# ADUM1250ARZ_v_01.net
KiCad netlist of a schematic drawn in EAGLE
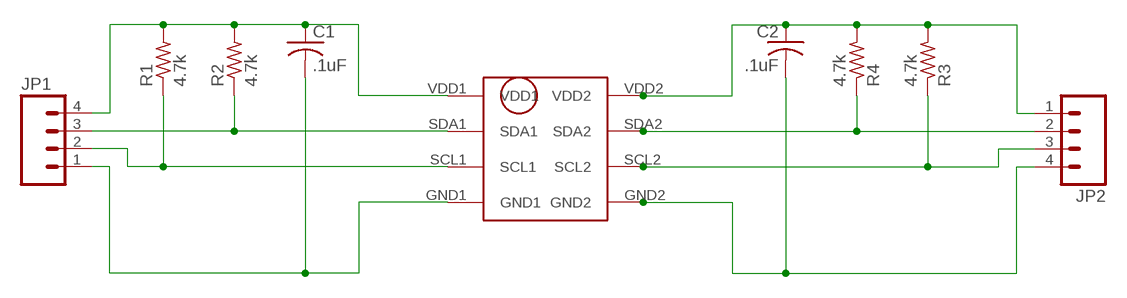
[diagram p0: schematic, sheet 1]

(export (version "E")
  (design (tool "Eeschema 10.0.6"))
  (components
    (comp (ref "C1")
      (value ".1uF")
      (footprint "eagle-import:C0805")
      (libsource (lib "eagle-import") (part "C-USC0805"))
    )
    (comp (ref "C2")
      (value ".1uF")
      (footprint "eagle-import:C0805")
      (libsource (lib "eagle-import") (part "C-USC0805"))
    )
    (comp (ref "JP1")
      (value "M04PTH")
      (footprint "eagle-import:1X04")
      (libsource (lib "eagle-import") (part "M04PTH"))
    )
    (comp (ref "JP2")
      (value "M04PTH")
      (footprint "eagle-import:1X04")
      (libsource (lib "eagle-import") (part "M04PTH"))
    )
    (comp (ref "R1")
      (value "4.7k")
      (footprint "eagle-import:R0805")
      (libsource (lib "eagle-import") (part "R-US_R0805"))
    )
    (comp (ref "R2")
      (value "4.7k")
      (footprint "eagle-import:R0805")
      (libsource (lib "eagle-import") (part "R-US_R0805"))
    )
    (comp (ref "R3")
      (value "4.7k")
      (footprint "eagle-import:R0805")
      (libsource (lib "eagle-import") (part "R-US_R0805"))
    )
    (comp (ref "R4")
      (value "4.7k")
      (footprint "eagle-import:R0805")
      (libsource (lib "eagle-import") (part "R-US_R0805"))
    )
    (comp (ref "U$1")
      (value "ADUM1250ARZ")
      (footprint "eagle-import:ADUM1250ARZ")
      (libsource (lib "eagle-import") (part "ADUM1250ARZ"))
    )
  )
  (nets
    (net (code "1") (name "Net-(C1-Pad1)") (class "Default")
      (node (ref "C1") (pin "1") (pinfunction "1_1") (pintype "passive"))
      (node (ref "JP1") (pin "4") (pinfunction "4_4") (pintype "passive"))
      (node (ref "R1") (pin "2") (pinfunction "2_2") (pintype "passive"))
      (node (ref "R2") (pin "2") (pinfunction "2_2") (pintype "passive"))
      (node (ref "U$1") (pin "VDD1") (pinfunction "VDD1_VDD1") (pintype "bidirectional"))
    )
    (net (code "2") (name "Net-(C1-Pad2)") (class "Default")
      (node (ref "C1") (pin "2") (pinfunction "2_2") (pintype "passive"))
      (node (ref "JP1") (pin "1") (pinfunction "1_1") (pintype "passive"))
      (node (ref "U$1") (pin "GND1") (pinfunction "GND1_GND1") (pintype "bidirectional"))
    )
    (net (code "3") (name "Net-(C2-Pad1)") (class "Default")
      (node (ref "C2") (pin "1") (pinfunction "1_1") (pintype "passive"))
      (node (ref "JP2") (pin "1") (pinfunction "1_1") (pintype "passive"))
      (node (ref "R3") (pin "2") (pinfunction "2_2") (pintype "passive"))
      (node (ref "R4") (pin "2") (pinfunction "2_2") (pintype "passive"))
      (node (ref "U$1") (pin "VDD2") (pinfunction "VDD2_VDD2") (pintype "bidirectional"))
    )
    (net (code "4") (name "Net-(C2-Pad2)") (class "Default")
      (node (ref "C2") (pin "2") (pinfunction "2_2") (pintype "passive"))
      (node (ref "JP2") (pin "4") (pinfunction "4_4") (pintype "passive"))
      (node (ref "U$1") (pin "GND2") (pinfunction "GND2_GND2") (pintype "bidirectional"))
    )
    (net (code "5") (name "Net-(JP1-Pad2)") (class "Default")
      (node (ref "JP1") (pin "2") (pinfunction "2_2") (pintype "passive"))
      (node (ref "R1") (pin "1") (pinfunction "1_1") (pintype "passive"))
      (node (ref "U$1") (pin "SCL1") (pinfunction "SCL1_SCL1") (pintype "bidirectional"))
    )
    (net (code "6") (name "Net-(JP1-Pad3)") (class "Default")
      (node (ref "JP1") (pin "3") (pinfunction "3_3") (pintype "passive"))
      (node (ref "R2") (pin "1") (pinfunction "1_1") (pintype "passive"))
      (node (ref "U$1") (pin "SDA1") (pinfunction "SDA1_SDA1") (pintype "bidirectional"))
    )
    (net (code "7") (name "Net-(JP2-Pad2)") (class "Default")
      (node (ref "JP2") (pin "2") (pinfunction "2_2") (pintype "passive"))
      (node (ref "R4") (pin "1") (pinfunction "1_1") (pintype "passive"))
      (node (ref "U$1") (pin "SDA2") (pinfunction "SDA2_SDA2") (pintype "bidirectional"))
    )
    (net (code "8") (name "Net-(JP2-Pad3)") (class "Default")
      (node (ref "JP2") (pin "3") (pinfunction "3_3") (pintype "passive"))
      (node (ref "R3") (pin "1") (pinfunction "1_1") (pintype "passive"))
      (node (ref "U$1") (pin "SCL2") (pinfunction "SCL2_SCL2") (pintype "bidirectional"))
    )
  )
)
